# investigator_oring.net
KiCad netlist of a schematic drawn in Altium Designer
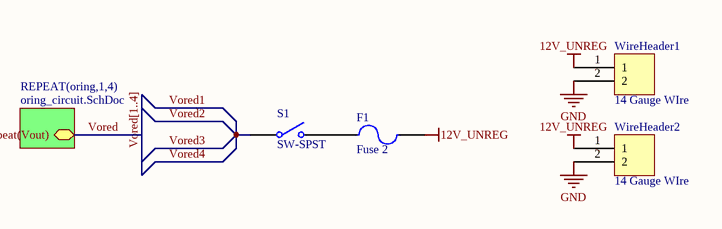
[diagram p0: investigator_oring.SchDoc]

(export (version "E")
  (design (tool "Eeschema 10.0.6"))
  (components
    (comp (ref "F1")
      (value "Fuse 2")
      (footprint "FUSE")
      (description "Fuse")
      (fields (field (name "PUBLISHER") "Altium Limited"))
      (libsource (lib "Miscellaneous Devices") (part "Fuse 2"))
    )
    (comp (ref "S1")
      (value "SW-SPST")
      (footprint "switch")
      (description "Single-Pole, Single-Throw Switch")
      (fields (field (name "PUBLISHER") "Altium Limited"))
      (libsource (lib "Miscellaneous Devices") (part "SW-SPST"))
    )
    (comp (ref "WireHeader1")
      (value "14 Gauge WIre")
      (footprint "WireHeader")
      (libsource (lib "investigator_oring") (part "WireHeader"))
    )
    (comp (ref "WireHeader2")
      (value "14 Gauge WIre")
      (footprint "WireHeader")
      (libsource (lib "investigator_oring") (part "WireHeader"))
    )
  )
  (nets
    (net (code "2") (name "/Vored4") (class "Default")
      (node (ref "S1") (pin "1") (pinfunction "COMMON_1") (pintype "passive"))
    )
    (net (code "4") (name "12V_UNREG") (class "Default")
      (node (ref "F1") (pin "2") (pinfunction "2_2") (pintype "passive"))
      (node (ref "WireHeader1") (pin "1") (pinfunction "1_1") (pintype "passive"))
      (node (ref "WireHeader2") (pin "1") (pinfunction "1_1") (pintype "passive"))
    )
    (net (code "5") (name "GND") (class "Default")
      (node (ref "WireHeader1") (pin "2") (pinfunction "2_2") (pintype "passive"))
      (node (ref "WireHeader2") (pin "2") (pinfunction "2_2") (pintype "passive"))
    )
    (net (code "6") (name "Net-(S1-NO)") (class "Default")
      (node (ref "F1") (pin "1") (pinfunction "1_1") (pintype "passive"))
      (node (ref "S1") (pin "2") (pinfunction "NO_2") (pintype "passive"))
    )
  )
)
